# 5v-3_3v_Stepdown_Breakout.net
KiCad netlist of a schematic drawn in EAGLE
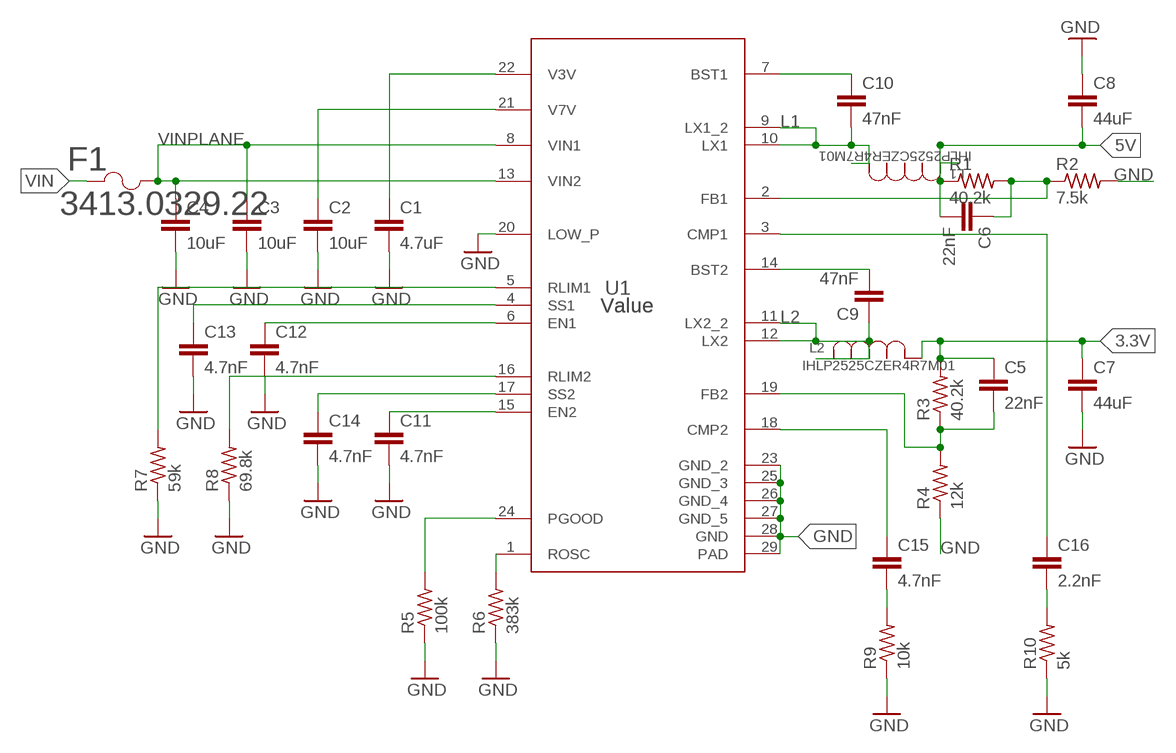
[diagram p0: schematic, sheet 1]

(export (version "E")
  (design (tool "Eeschema 10.0.6"))
  (components
    (comp (ref "C1")
      (value "4.7uF")
      (footprint "eagle-import:0402-TIGHT")
      (libsource (lib "eagle-import") (part "4.7UF-0402_TIGHT-6.3V-20%-X5R"))
    )
    (comp (ref "C2")
      (value "10uF")
      (footprint "eagle-import:0603")
      (libsource (lib "eagle-import") (part "10UF-0603-6.3V-20%"))
    )
    (comp (ref "C3")
      (value "10uF")
      (footprint "eagle-import:0603")
      (libsource (lib "eagle-import") (part "10UF-0603-6.3V-20%"))
    )
    (comp (ref "C4")
      (value "10uF")
      (footprint "eagle-import:0603")
      (libsource (lib "eagle-import") (part "10UF-0603-6.3V-20%"))
    )
    (comp (ref "C5")
      (value "22nF")
      (footprint "eagle-import:0402")
      (libsource (lib "eagle-import") (part "22NF/22,000PF-0603-25V-10%-X7R"))
    )
    (comp (ref "C6")
      (value "22nF")
      (footprint "eagle-import:0402")
      (libsource (lib "eagle-import") (part "22NF/22,000PF-0603-25V-10%-X7R"))
    )
    (comp (ref "C7")
      (value "44uF")
      (footprint "eagle-import:0402")
      (libsource (lib "eagle-import") (part "6PF-0402-50V-0.5%"))
    )
    (comp (ref "C8")
      (value "44uF")
      (footprint "eagle-import:0402")
      (libsource (lib "eagle-import") (part "6PF-0402-50V-0.5%"))
    )
    (comp (ref "C9")
      (value "47nF")
      (footprint "eagle-import:0402-TIGHT")
      (libsource (lib "eagle-import") (part "47NF-0402_TIGHT-25V-10%-X7R"))
    )
    (comp (ref "C10")
      (value "47nF")
      (footprint "eagle-import:0402-TIGHT")
      (libsource (lib "eagle-import") (part "47NF-0402_TIGHT-25V-10%-X7R"))
    )
    (comp (ref "C11")
      (value "4.7nF")
      (footprint "eagle-import:0402-TIGHT")
      (libsource (lib "eagle-import") (part "47NF-0402_TIGHT-25V-10%-X7R"))
    )
    (comp (ref "C12")
      (value "4.7nF")
      (footprint "eagle-import:0402-TIGHT")
      (libsource (lib "eagle-import") (part "47NF-0402_TIGHT-25V-10%-X7R"))
    )
    (comp (ref "C13")
      (value "4.7nF")
      (footprint "eagle-import:0402-TIGHT")
      (libsource (lib "eagle-import") (part "47NF-0402_TIGHT-25V-10%-X7R"))
    )
    (comp (ref "C14")
      (value "4.7nF")
      (footprint "eagle-import:0402-TIGHT")
      (libsource (lib "eagle-import") (part "47NF-0402_TIGHT-25V-10%-X7R"))
    )
    (comp (ref "C15")
      (value "4.7nF")
      (footprint "eagle-import:0402-TIGHT")
      (libsource (lib "eagle-import") (part "47NF-0402_TIGHT-25V-10%-X7R"))
    )
    (comp (ref "C16")
      (value "2.2nF")
      (footprint "eagle-import:0402-TIGHT")
      (libsource (lib "eagle-import") (part "47NF-0402_TIGHT-25V-10%-X7R"))
    )
    (comp (ref "F1")
      (value "3413.0329.22")
      (footprint "eagle-import:FUS_SCHURTER_3413_SCH")
      (libsource (lib "eagle-import") (part "3413.0329.22"))
    )
    (comp (ref "L1")
      (value "IHLP2525CZER4R7M01")
      (footprint "eagle-import:IND25X25CZ")
      (libsource (lib "eagle-import") (part "IHLP2525CZER4R7M01"))
    )
    (comp (ref "L2")
      (value "IHLP2525CZER4R7M01")
      (footprint "eagle-import:IND25X25CZ")
      (libsource (lib "eagle-import") (part "IHLP2525CZER4R7M01"))
    )
    (comp (ref "R1")
      (value "40.2k")
      (footprint "eagle-import:R0402")
      (libsource (lib "eagle-import") (part "R-US_R0402"))
    )
    (comp (ref "R2")
      (value "7.5k")
      (footprint "eagle-import:R0402")
      (libsource (lib "eagle-import") (part "R-US_R0402"))
    )
    (comp (ref "R3")
      (value "40.2k")
      (footprint "eagle-import:R0402")
      (libsource (lib "eagle-import") (part "R-US_R0402"))
    )
    (comp (ref "R4")
      (value "12k")
      (footprint "eagle-import:R0402")
      (libsource (lib "eagle-import") (part "R-US_R0402"))
    )
    (comp (ref "R5")
      (value "100k")
      (footprint "eagle-import:R0402")
      (libsource (lib "eagle-import") (part "R-US_R0402"))
    )
    (comp (ref "R6")
      (value "383k")
      (footprint "eagle-import:R0402")
      (libsource (lib "eagle-import") (part "R-US_R0402"))
    )
    (comp (ref "R7")
      (value "59k")
      (footprint "eagle-import:R0402")
      (libsource (lib "eagle-import") (part "R-US_R0402"))
    )
    (comp (ref "R8")
      (value "69.8k")
      (footprint "eagle-import:R0402")
      (libsource (lib "eagle-import") (part "R-US_R0402"))
    )
    (comp (ref "R9")
      (value "10k")
      (footprint "eagle-import:R0402")
      (libsource (lib "eagle-import") (part "R-US_R0402"))
    )
    (comp (ref "R10")
      (value "5k")
      (footprint "eagle-import:R0402")
      (libsource (lib "eagle-import") (part "R-US_R0402"))
    )
    (comp (ref "U1")
      (value "Value")
      (footprint "eagle-import:RHD0028A")
      (fields (field (name "MANUFACTURER") "Texas Instruments") (field (name "PARTNUMBER") "TPS65253RHDR"))
      (libsource (lib "eagle-import") (part "TPS65253RHDR"))
    )
  )
  (nets
    (net (code "1") (name "/L1") (class "Default")
      (node (ref "C10") (pin "2") (pinfunction "2_2") (pintype "passive"))
      (node (ref "L1") (pin "1") (pinfunction "1_1") (pintype "passive"))
      (node (ref "U1") (pin "10") (pinfunction "LX1_10") (pintype "power_in"))
      (node (ref "U1") (pin "9") (pinfunction "LX1_2_9") (pintype "power_in"))
    )
    (net (code "2") (name "/L2") (class "Default")
      (node (ref "C9") (pin "1") (pinfunction "1_1") (pintype "passive"))
      (node (ref "L2") (pin "2") (pinfunction "2_2") (pintype "passive"))
      (node (ref "U1") (pin "11") (pinfunction "LX2_2_11") (pintype "power_in"))
      (node (ref "U1") (pin "12") (pinfunction "LX2_12") (pintype "power_in"))
    )
    (net (code "3") (name "/VINPLANE") (class "Default")
      (node (ref "C3") (pin "1") (pinfunction "1_1") (pintype "passive"))
      (node (ref "C4") (pin "1") (pinfunction "1_1") (pintype "passive"))
      (node (ref "F1") (pin "2") (pinfunction "2_2") (pintype "passive"))
      (node (ref "U1") (pin "13") (pinfunction "VIN2_13") (pintype "power_in"))
      (node (ref "U1") (pin "8") (pinfunction "VIN1_8") (pintype "power_in"))
    )
    (net (code "4") (name "3.3V") (class "Default")
      (node (ref "C5") (pin "1") (pinfunction "1_1") (pintype "passive"))
      (node (ref "C7") (pin "1") (pinfunction "1_1") (pintype "passive"))
      (node (ref "L2") (pin "1") (pinfunction "1_1") (pintype "passive"))
      (node (ref "R3") (pin "2") (pinfunction "2_2") (pintype "passive"))
    )
    (net (code "5") (name "5V") (class "Default")
      (node (ref "C6") (pin "2") (pinfunction "2_2") (pintype "passive"))
      (node (ref "C8") (pin "2") (pinfunction "2_2") (pintype "passive"))
      (node (ref "L1") (pin "2") (pinfunction "2_2") (pintype "passive"))
      (node (ref "R1") (pin "1") (pinfunction "1_1") (pintype "passive"))
    )
    (net (code "6") (name "GND") (class "Default")
      (node (ref "C1") (pin "2") (pinfunction "2_2") (pintype "passive"))
      (node (ref "C11") (pin "2") (pinfunction "2_2") (pintype "passive"))
      (node (ref "C12") (pin "2") (pinfunction "2_2") (pintype "passive"))
      (node (ref "C13") (pin "2") (pinfunction "2_2") (pintype "passive"))
      (node (ref "C14") (pin "2") (pinfunction "2_2") (pintype "passive"))
      (node (ref "C2") (pin "2") (pinfunction "2_2") (pintype "passive"))
      (node (ref "C3") (pin "2") (pinfunction "2_2") (pintype "passive"))
      (node (ref "C4") (pin "2") (pinfunction "2_2") (pintype "passive"))
      (node (ref "C7") (pin "2") (pinfunction "2_2") (pintype "passive"))
      (node (ref "C8") (pin "1") (pinfunction "1_1") (pintype "passive"))
      (node (ref "R10") (pin "1") (pinfunction "1_1") (pintype "passive"))
      (node (ref "R2") (pin "2") (pinfunction "2_2") (pintype "passive"))
      (node (ref "R4") (pin "1") (pinfunction "1_1") (pintype "passive"))
      (node (ref "R5") (pin "1") (pinfunction "1_1") (pintype "passive"))
      (node (ref "R6") (pin "1") (pinfunction "1_1") (pintype "passive"))
      (node (ref "R7") (pin "1") (pinfunction "1_1") (pintype "passive"))
      (node (ref "R8") (pin "1") (pinfunction "1_1") (pintype "passive"))
      (node (ref "R9") (pin "1") (pinfunction "1_1") (pintype "passive"))
      (node (ref "U1") (pin "20") (pinfunction "LOW_P_20") (pintype "input"))
      (node (ref "U1") (pin "23") (pinfunction "GND_2_23") (pintype "power_in"))
      (node (ref "U1") (pin "25") (pinfunction "GND_3_25") (pintype "power_in"))
      (node (ref "U1") (pin "26") (pinfunction "GND_4_26") (pintype "power_in"))
      (node (ref "U1") (pin "27") (pinfunction "GND_5_27") (pintype "power_in"))
      (node (ref "U1") (pin "28") (pinfunction "GND_28") (pintype "power_in"))
      (node (ref "U1") (pin "29") (pinfunction "PAD_29") (pintype "power_in"))
    )
    (net (code "7") (name "Net-(C15-Pad2)") (class "Default")
      (node (ref "C15") (pin "2") (pinfunction "2_2") (pintype "passive"))
      (node (ref "R9") (pin "2") (pinfunction "2_2") (pintype "passive"))
    )
    (net (code "8") (name "Net-(C16-Pad2)") (class "Default")
      (node (ref "C16") (pin "2") (pinfunction "2_2") (pintype "passive"))
      (node (ref "R10") (pin "2") (pinfunction "2_2") (pintype "passive"))
    )
    (net (code "9") (name "Net-(U1-BST1)") (class "Default")
      (node (ref "C10") (pin "1") (pinfunction "1_1") (pintype "passive"))
      (node (ref "U1") (pin "7") (pinfunction "BST1_7") (pintype "power_in"))
    )
    (net (code "10") (name "Net-(U1-BST2)") (class "Default")
      (node (ref "C9") (pin "2") (pinfunction "2_2") (pintype "passive"))
      (node (ref "U1") (pin "14") (pinfunction "BST2_14") (pintype "power_in"))
    )
    (net (code "11") (name "Net-(U1-CMP1)") (class "Default")
      (node (ref "C16") (pin "1") (pinfunction "1_1") (pintype "passive"))
      (node (ref "U1") (pin "3") (pinfunction "CMP1_3") (pintype "output"))
    )
    (net (code "12") (name "Net-(U1-CMP2)") (class "Default")
      (node (ref "C15") (pin "1") (pinfunction "1_1") (pintype "passive"))
      (node (ref "U1") (pin "18") (pinfunction "CMP2_18") (pintype "output"))
    )
    (net (code "13") (name "Net-(U1-EN1)") (class "Default")
      (node (ref "C12") (pin "1") (pinfunction "1_1") (pintype "passive"))
      (node (ref "U1") (pin "6") (pinfunction "EN1_6") (pintype "input"))
    )
    (net (code "14") (name "Net-(U1-EN2)") (class "Default")
      (node (ref "C11") (pin "1") (pinfunction "1_1") (pintype "passive"))
      (node (ref "U1") (pin "15") (pinfunction "EN2_15") (pintype "input"))
    )
    (net (code "15") (name "Net-(U1-FB1)") (class "Default")
      (node (ref "C6") (pin "1") (pinfunction "1_1") (pintype "passive"))
      (node (ref "R1") (pin "2") (pinfunction "2_2") (pintype "passive"))
      (node (ref "R2") (pin "1") (pinfunction "1_1") (pintype "passive"))
      (node (ref "U1") (pin "2") (pinfunction "FB1_2") (pintype "input"))
    )
    (net (code "16") (name "Net-(U1-FB2)") (class "Default")
      (node (ref "C5") (pin "2") (pinfunction "2_2") (pintype "passive"))
      (node (ref "R3") (pin "1") (pinfunction "1_1") (pintype "passive"))
      (node (ref "R4") (pin "2") (pinfunction "2_2") (pintype "passive"))
      (node (ref "U1") (pin "19") (pinfunction "FB2_19") (pintype "input"))
    )
    (net (code "17") (name "Net-(U1-PGOOD)") (class "Default")
      (node (ref "R5") (pin "2") (pinfunction "2_2") (pintype "passive"))
      (node (ref "U1") (pin "24") (pinfunction "PGOOD_24") (pintype "open_collector"))
    )
    (net (code "18") (name "Net-(U1-RLIM1)") (class "Default")
      (node (ref "R7") (pin "2") (pinfunction "2_2") (pintype "passive"))
      (node (ref "U1") (pin "5") (pinfunction "RLIM1_5") (pintype "input"))
    )
    (net (code "19") (name "Net-(U1-RLIM2)") (class "Default")
      (node (ref "R8") (pin "2") (pinfunction "2_2") (pintype "passive"))
      (node (ref "U1") (pin "16") (pinfunction "RLIM2_16") (pintype "input"))
    )
    (net (code "20") (name "Net-(U1-ROSC)") (class "Default")
      (node (ref "R6") (pin "2") (pinfunction "2_2") (pintype "passive"))
      (node (ref "U1") (pin "1") (pinfunction "ROSC_1") (pintype "input"))
    )
    (net (code "21") (name "Net-(U1-SS1)") (class "Default")
      (node (ref "C13") (pin "1") (pinfunction "1_1") (pintype "passive"))
      (node (ref "U1") (pin "4") (pinfunction "SS1_4") (pintype "input"))
    )
    (net (code "22") (name "Net-(U1-SS2)") (class "Default")
      (node (ref "C14") (pin "1") (pinfunction "1_1") (pintype "passive"))
      (node (ref "U1") (pin "17") (pinfunction "SS2_17") (pintype "input"))
    )
    (net (code "23") (name "Net-(U1-V3V)") (class "Default")
      (node (ref "C1") (pin "1") (pinfunction "1_1") (pintype "passive"))
      (node (ref "U1") (pin "22") (pinfunction "V3V_22") (pintype "power_in"))
    )
    (net (code "24") (name "Net-(U1-V7V)") (class "Default")
      (node (ref "C2") (pin "1") (pinfunction "1_1") (pintype "passive"))
      (node (ref "U1") (pin "21") (pinfunction "V7V_21") (pintype "power_in"))
    )
    (net (code "25") (name "VIN") (class "Default")
      (node (ref "F1") (pin "1") (pinfunction "1_1") (pintype "passive"))
    )
  )
)
